# ACme.net
KiCad netlist of a schematic drawn in EAGLE
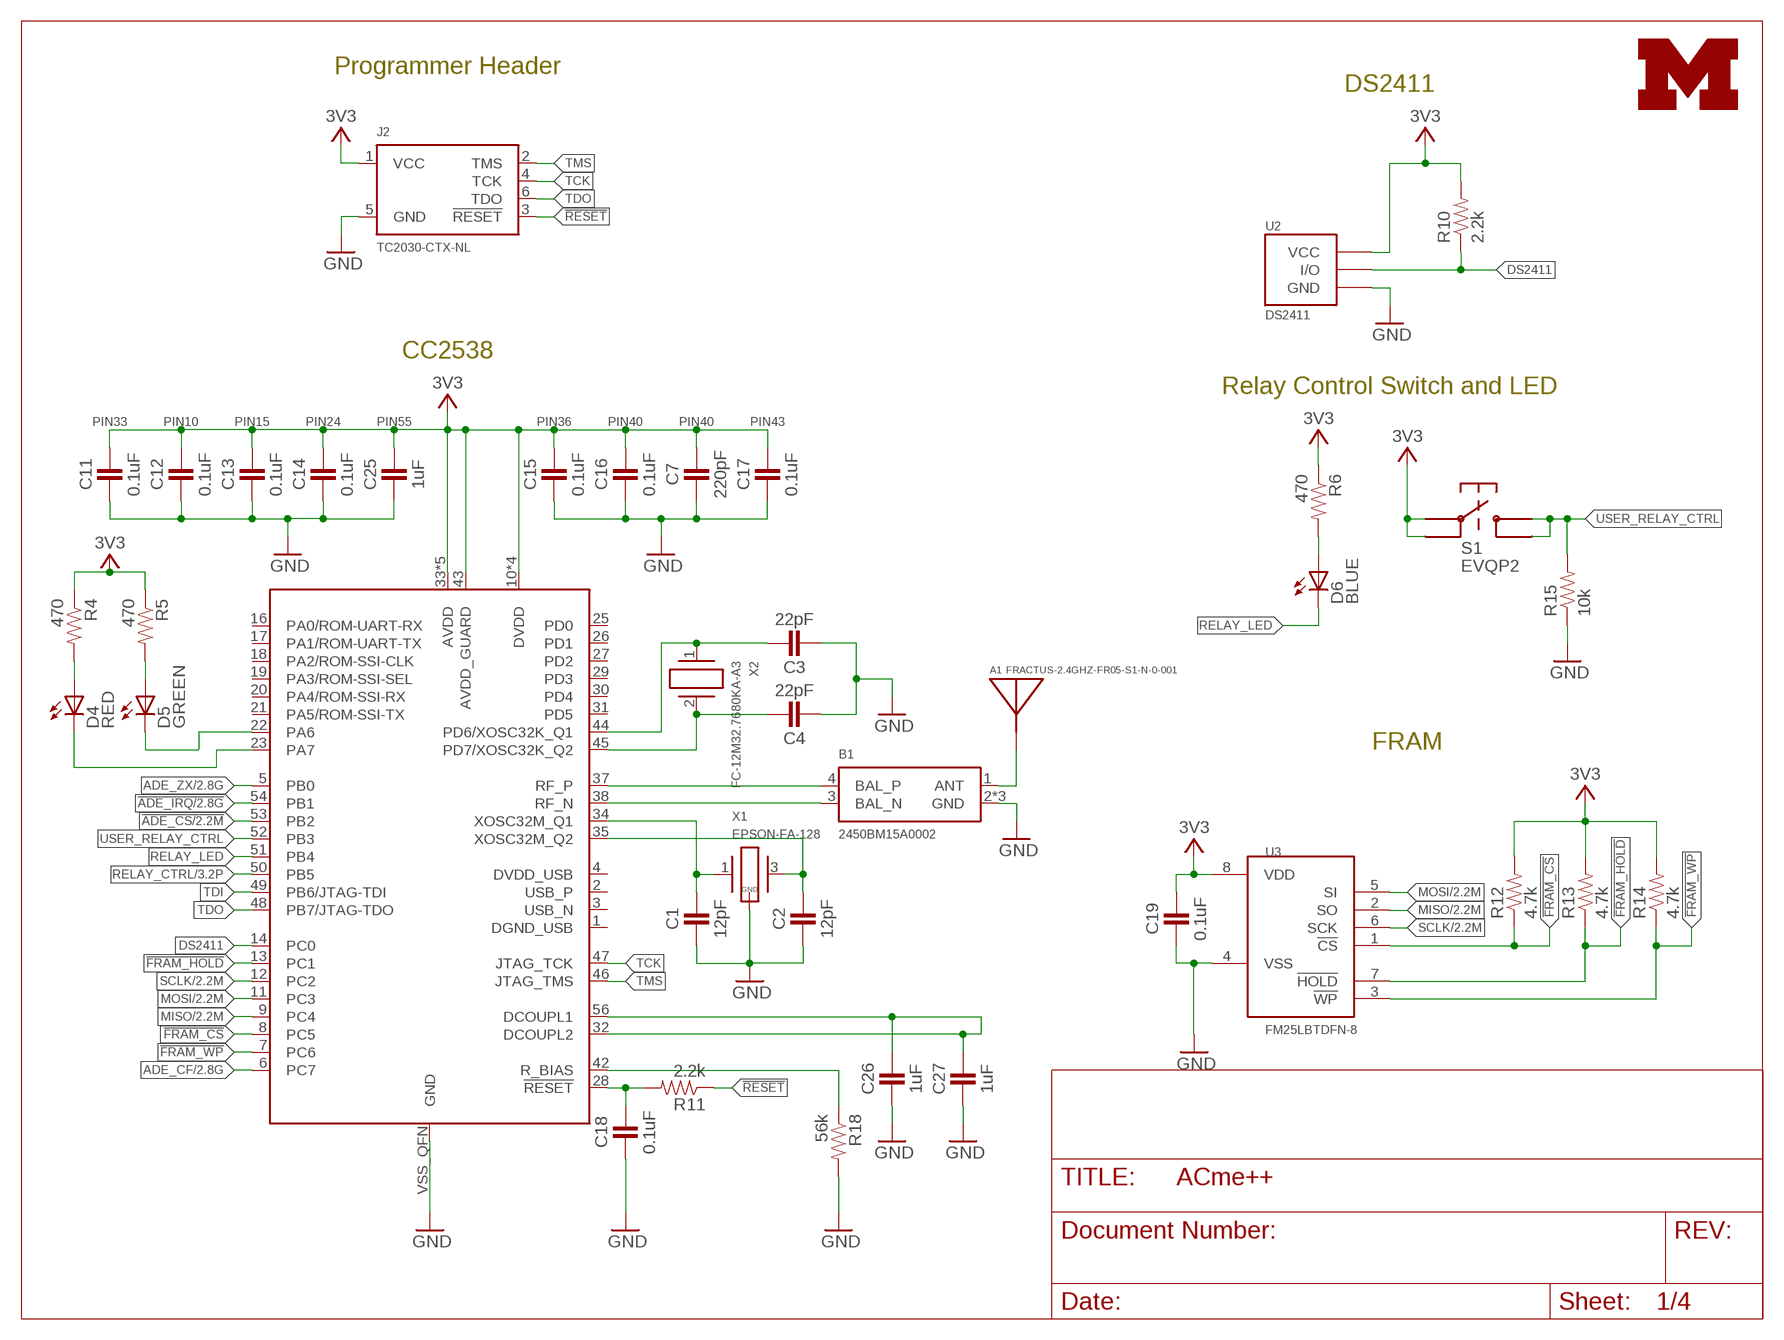
[diagram p0: schematic, sheet 1]
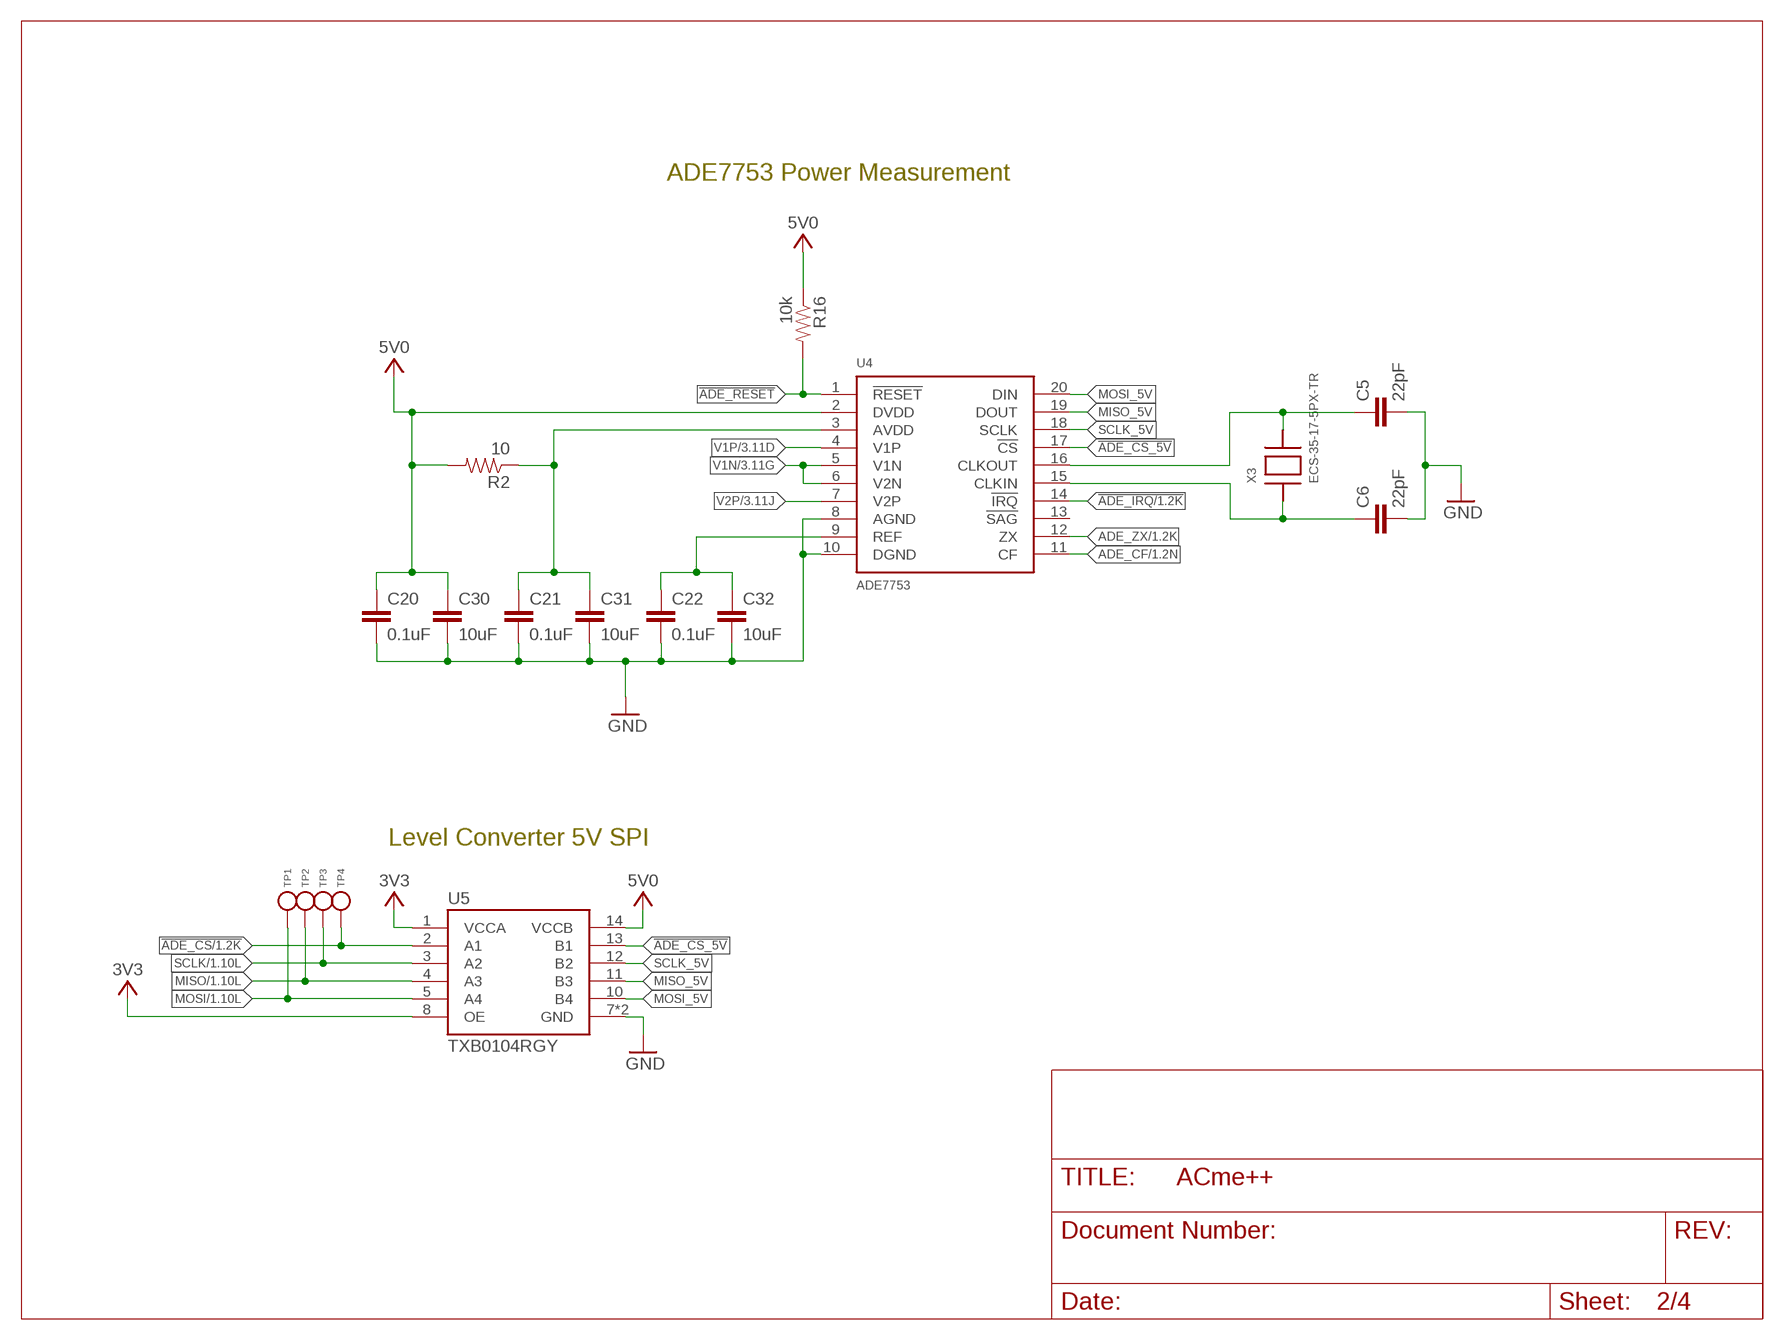
[diagram p1: schematic, sheet 2]
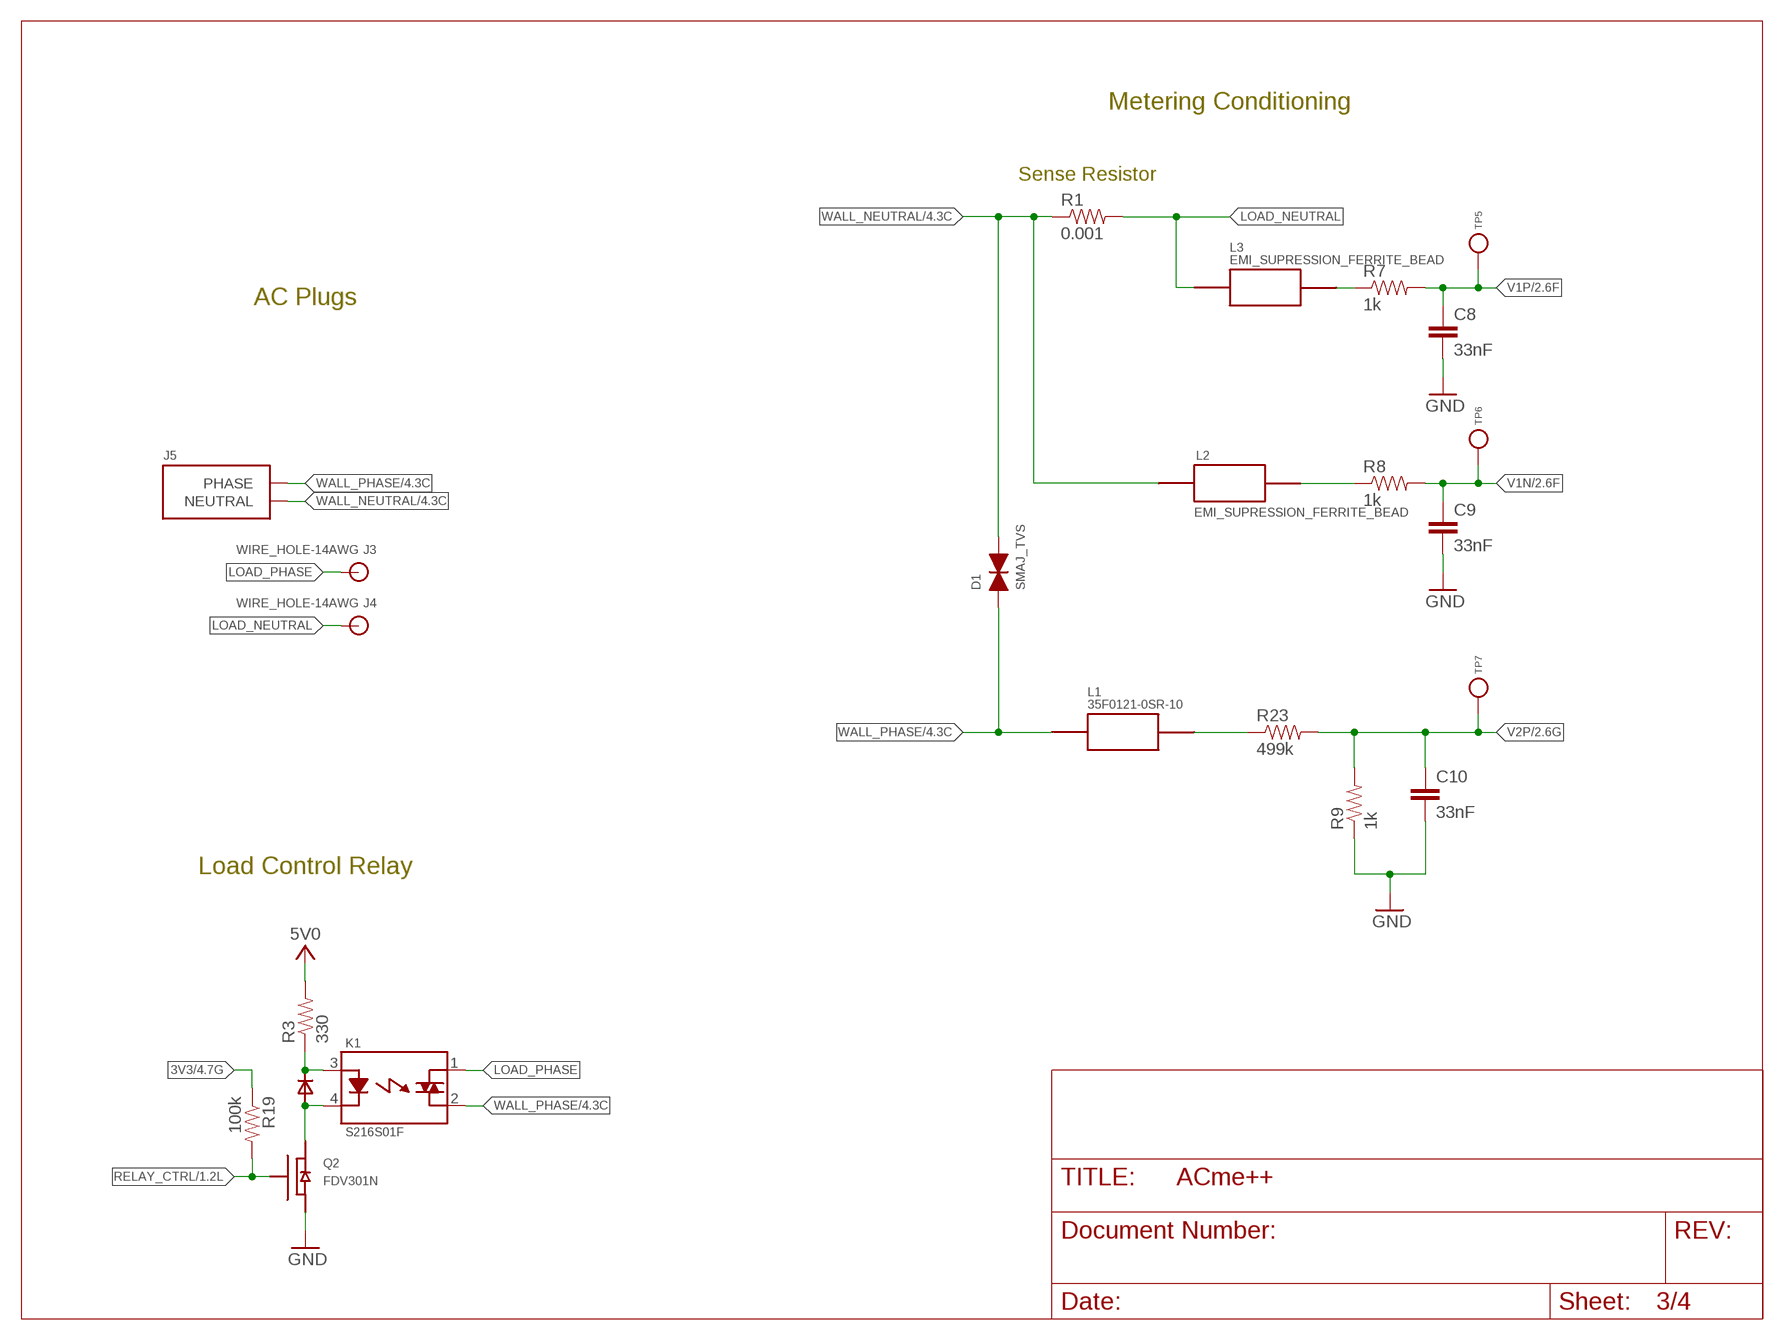
[diagram p2: schematic, sheet 3]
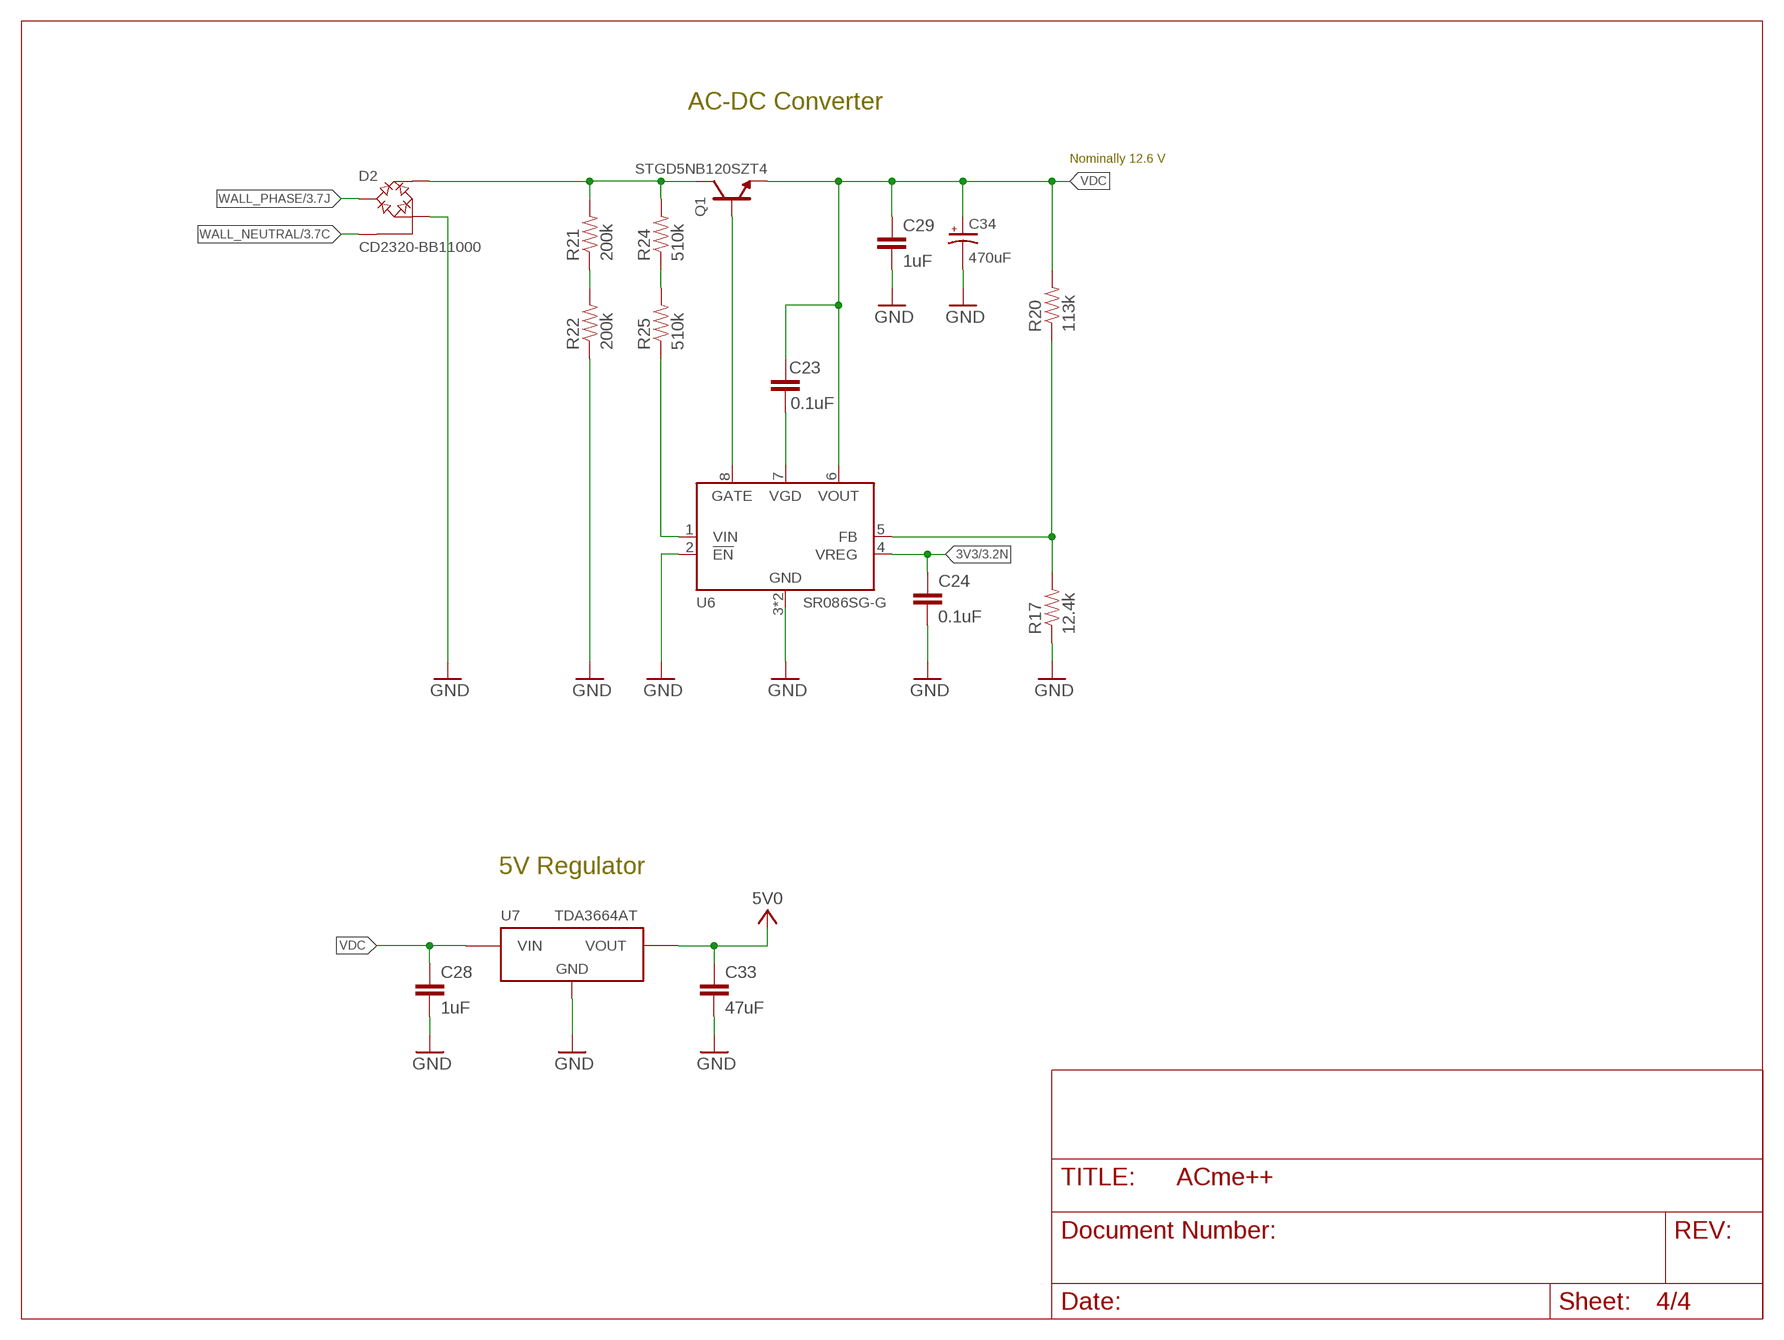
[diagram p3: schematic, sheet 4]

(export (version "E")
  (design (tool "Eeschema 10.0.6"))
  (components
    (comp (ref "C5")
      (value "22pF")
      (footprint "eagle-import:0603-CAP")
      (libsource (lib "eagle-import") (part "CAP0603-CAP"))
    )
    (comp (ref "C6")
      (value "22pF")
      (footprint "eagle-import:0603-CAP")
      (libsource (lib "eagle-import") (part "CAP0603-CAP"))
    )
    (comp (ref "C20")
      (value "0.1uF")
      (footprint "eagle-import:0603-CAP")
      (libsource (lib "eagle-import") (part "CAP0603-CAP"))
    )
    (comp (ref "C21")
      (value "0.1uF")
      (footprint "eagle-import:0603-CAP")
      (libsource (lib "eagle-import") (part "CAP0603-CAP"))
    )
    (comp (ref "C22")
      (value "0.1uF")
      (footprint "eagle-import:0603-CAP")
      (libsource (lib "eagle-import") (part "CAP0603-CAP"))
    )
    (comp (ref "C30")
      (value "10uF")
      (footprint "eagle-import:0603-CAP")
      (libsource (lib "eagle-import") (part "CAP0603-CAP"))
    )
    (comp (ref "C31")
      (value "10uF")
      (footprint "eagle-import:0603-CAP")
      (libsource (lib "eagle-import") (part "CAP0603-CAP"))
    )
    (comp (ref "C32")
      (value "10uF")
      (footprint "eagle-import:0603-CAP")
      (libsource (lib "eagle-import") (part "CAP0603-CAP"))
    )
    (comp (ref "R2")
      (value "10")
      (footprint "eagle-import:0603-RES")
      (libsource (lib "eagle-import") (part "RESISTOR0603-RES"))
    )
    (comp (ref "R16")
      (value "10k")
      (footprint "eagle-import:0603-RES")
      (libsource (lib "eagle-import") (part "RESISTOR0603-RES"))
    )
    (comp (ref "TP1")
      (value "TEST_POINT_0.040IN")
      (footprint "eagle-import:TESTPOINT_0.040IN")
      (libsource (lib "eagle-import") (part "TEST_POINT_0.040IN"))
    )
    (comp (ref "TP2")
      (value "TEST_POINT_0.040IN")
      (footprint "eagle-import:TESTPOINT_0.040IN")
      (libsource (lib "eagle-import") (part "TEST_POINT_0.040IN"))
    )
    (comp (ref "TP3")
      (value "TEST_POINT_0.040IN")
      (footprint "eagle-import:TESTPOINT_0.040IN")
      (libsource (lib "eagle-import") (part "TEST_POINT_0.040IN"))
    )
    (comp (ref "TP4")
      (value "TEST_POINT_0.040IN")
      (footprint "eagle-import:TESTPOINT_0.040IN")
      (libsource (lib "eagle-import") (part "TEST_POINT_0.040IN"))
    )
    (comp (ref "U4")
      (value "ADE7753")
      (footprint "eagle-import:SSOP-20")
      (fields (field (name "MOUSER") " 584-ADE7753ARSZR "))
      (libsource (lib "eagle-import") (part "ADE7753"))
    )
    (comp (ref "U5")
      (value "TXB0104RGY")
      (footprint "eagle-import:S-PVQFN-N14")
      (libsource (lib "eagle-import") (part "TXB0104RGY"))
    )
    (comp (ref "X3")
      (value "ECS-35-17-5PX-TR")
      (footprint "eagle-import:CSM-7X")
      (libsource (lib "eagle-import") (part "ECS-35-17-5PX-TR"))
    )
    (comp (ref "C8")
      (value "33nF")
      (footprint "eagle-import:0805")
      (libsource (lib "eagle-import") (part "CAP0805"))
    )
    (comp (ref "C9")
      (value "33nF")
      (footprint "eagle-import:0805")
      (libsource (lib "eagle-import") (part "CAP0805"))
    )
    (comp (ref "C10")
      (value "33nF")
      (footprint "eagle-import:0805")
      (libsource (lib "eagle-import") (part "CAP0805"))
    )
    (comp (ref "D1")
      (value "SMAJ_TVS")
      (footprint "eagle-import:DO214_TVS")
      (libsource (lib "eagle-import") (part "SMAJ_TVS"))
    )
    (comp (ref "D3")
      (value "DIODE_MMBD914")
      (footprint "eagle-import:SOT-23")
      (libsource (lib "eagle-import") (part "DIODE_MMBD914"))
    )
    (comp (ref "J3")
      (value "WIRE_HOLE-14AWG")
      (footprint "eagle-import:WIRE_HOLE-14AWG")
      (libsource (lib "eagle-import") (part "WIRE_HOLE-14AWG"))
    )
    (comp (ref "J4")
      (value "WIRE_HOLE-14AWG")
      (footprint "eagle-import:WIRE_HOLE-14AWG")
      (libsource (lib "eagle-import") (part "WIRE_HOLE-14AWG"))
    )
    (comp (ref "J5")
      (value "AC-PLUG-2")
      (footprint "eagle-import:AC_MALE_PINS_2")
      (libsource (lib "eagle-import") (part "AC-PLUG-2"))
    )
    (comp (ref "K1")
      (value "S216S01F")
      (footprint "eagle-import:RELAY_SX16S0X")
      (libsource (lib "eagle-import") (part "S216S01F"))
    )
    (comp (ref "L1")
      (value "35F0121-0SR-10")
      (footprint "eagle-import:35F0102")
      (libsource (lib "eagle-import") (part "35F0121-0SR-10"))
    )
    (comp (ref "L2")
      (value "EMI_SUPRESSION_FERRITE_BEAD")
      (footprint "eagle-import:L1806")
      (libsource (lib "eagle-import") (part "EMI_SUPRESSION_FERRITE_BEAD"))
    )
    (comp (ref "L3")
      (value "EMI_SUPRESSION_FERRITE_BEAD")
      (footprint "eagle-import:L1806")
      (libsource (lib "eagle-import") (part "EMI_SUPRESSION_FERRITE_BEAD"))
    )
    (comp (ref "Q2")
      (value "FDV301N")
      (footprint "eagle-import:SOT-23")
      (libsource (lib "eagle-import") (part "FDV301N"))
    )
    (comp (ref "R1")
      (value "0.001")
      (footprint "eagle-import:R2512")
      (libsource (lib "eagle-import") (part "SparkFun-Resistors_RESISTOR2512"))
    )
    (comp (ref "R3")
      (value "330")
      (footprint "eagle-import:0805")
      (libsource (lib "eagle-import") (part "RESISTOR0805-RES"))
    )
    (comp (ref "R7")
      (value "1k")
      (footprint "eagle-import:0805")
      (libsource (lib "eagle-import") (part "RESISTOR0805-RES"))
    )
    (comp (ref "R8")
      (value "1k")
      (footprint "eagle-import:0805")
      (libsource (lib "eagle-import") (part "RESISTOR0805-RES"))
    )
    (comp (ref "R9")
      (value "1k")
      (footprint "eagle-import:0805")
      (libsource (lib "eagle-import") (part "RESISTOR0805-RES"))
    )
    (comp (ref "R19")
      (value "100k")
      (footprint "eagle-import:0603-RES")
      (libsource (lib "eagle-import") (part "RESISTOR0603-RES"))
    )
    (comp (ref "R23")
      (value "499k")
      (footprint "eagle-import:0805")
      (libsource (lib "eagle-import") (part "RESISTOR0805-RES"))
    )
    (comp (ref "TP5")
      (value "TEST_POINT_0.040IN")
      (footprint "eagle-import:TESTPOINT_0.040IN")
      (libsource (lib "eagle-import") (part "TEST_POINT_0.040IN"))
    )
    (comp (ref "TP6")
      (value "TEST_POINT_0.040IN")
      (footprint "eagle-import:TESTPOINT_0.040IN")
      (libsource (lib "eagle-import") (part "TEST_POINT_0.040IN"))
    )
    (comp (ref "TP7")
      (value "TEST_POINT_0.040IN")
      (footprint "eagle-import:TESTPOINT_0.040IN")
      (libsource (lib "eagle-import") (part "TEST_POINT_0.040IN"))
    )
    (comp (ref "C23")
      (value "0.1uF")
      (footprint "eagle-import:0603-CAP")
      (libsource (lib "eagle-import") (part "CAP0603-CAP"))
    )
    (comp (ref "C24")
      (value "0.1uF")
      (footprint "eagle-import:0603-CAP")
      (libsource (lib "eagle-import") (part "CAP0603-CAP"))
    )
    (comp (ref "C28")
      (value "1uF")
      (footprint "eagle-import:0603-CAP")
      (libsource (lib "eagle-import") (part "CAP0603-CAP"))
    )
    (comp (ref "C29")
      (value "1uF")
      (footprint "eagle-import:1206")
      (libsource (lib "eagle-import") (part "CAP1206"))
    )
    (comp (ref "C33")
      (value "47uF")
      (footprint "eagle-import:1206")
      (libsource (lib "eagle-import") (part "CAP1206"))
    )
    (comp (ref "C34")
      (value "470uF")
      (footprint "eagle-import:CAP_SM_10MM")
      (libsource (lib "eagle-import") (part "CAP_EEE-FP1E471AP"))
    )
    (comp (ref "D2")
      (value "CD2320-BB11000")
      (footprint "eagle-import:CD2320")
      (libsource (lib "eagle-import") (part "CD2320-BB11000"))
    )
    (comp (ref "Q1")
      (value "STGD5NB120SZT4")
      (footprint "eagle-import:DPAK")
      (libsource (lib "eagle-import") (part "STGD5NB120SZT4"))
    )
    (comp (ref "R17")
      (value "12.4k")
      (footprint "eagle-import:0603-RES")
      (libsource (lib "eagle-import") (part "SparkFun-Resistors_RESISTOR0603-RES"))
    )
    (comp (ref "R20")
      (value "113k")
      (footprint "eagle-import:0603-RES")
      (libsource (lib "eagle-import") (part "SparkFun-Resistors_RESISTOR0603-RES"))
    )
    (comp (ref "R21")
      (value "200k")
      (footprint "eagle-import:1206")
      (libsource (lib "eagle-import") (part "SparkFun-Resistors_RESISTOR1206"))
    )
    (comp (ref "R22")
      (value "200k")
      (footprint "eagle-import:1206")
      (libsource (lib "eagle-import") (part "SparkFun-Resistors_RESISTOR1206"))
    )
    (comp (ref "R24")
      (value "510k")
      (footprint "eagle-import:1206")
      (libsource (lib "eagle-import") (part "SparkFun-Resistors_RESISTOR1206"))
    )
    (comp (ref "R25")
      (value "510k")
      (footprint "eagle-import:1206")
      (libsource (lib "eagle-import") (part "SparkFun-Resistors_RESISTOR1206"))
    )
    (comp (ref "U6")
      (value "SR086SG-G")
      (footprint "eagle-import:SR086")
      (libsource (lib "eagle-import") (part "SR086SG-G"))
    )
    (comp (ref "U7")
      (value "TDA3664AT")
      (footprint "eagle-import:SOIC_8")
      (libsource (lib "eagle-import") (part "TDA3664AT"))
    )
    (comp (ref "A1")
      (value "FRACTUS-2.4GHZ-FR05-S1-N-0-001")
      (footprint "eagle-import:FRACTUS-ANTENNA-FR05-S1-N-0-001")
      (libsource (lib "eagle-import") (part "FRACTUS-2.4GHZ-FR05-S1-N-0-001"))
    )
    (comp (ref "B1")
      (value "2450BM15A0002")
      (footprint "eagle-import:2450BM")
      (libsource (lib "eagle-import") (part "2450BM15A0002"))
    )
    (comp (ref "C1")
      (value "12pF")
      (footprint "eagle-import:0402_CAP")
      (libsource (lib "eagle-import") (part "CAPACITOR"))
    )
    (comp (ref "C2")
      (value "12pF")
      (footprint "eagle-import:0402_CAP")
      (libsource (lib "eagle-import") (part "CAPACITOR"))
    )
    (comp (ref "C3")
      (value "22pF")
      (footprint "eagle-import:0402_CAP")
      (libsource (lib "eagle-import") (part "CAPACITOR"))
    )
    (comp (ref "C4")
      (value "22pF")
      (footprint "eagle-import:0402_CAP")
      (libsource (lib "eagle-import") (part "CAPACITOR"))
    )
    (comp (ref "C7")
      (value "220pF")
      (footprint "eagle-import:0402_CAP")
      (libsource (lib "eagle-import") (part "CAPACITOR"))
    )
    (comp (ref "C11")
      (value "0.1uF")
      (footprint "eagle-import:0402_CAP")
      (libsource (lib "eagle-import") (part "CAPACITOR"))
    )
    (comp (ref "C12")
      (value "0.1uF")
      (footprint "eagle-import:0402_CAP")
      (libsource (lib "eagle-import") (part "CAPACITOR"))
    )
    (comp (ref "C13")
      (value "0.1uF")
      (footprint "eagle-import:0402_CAP")
      (libsource (lib "eagle-import") (part "CAPACITOR"))
    )
    (comp (ref "C14")
      (value "0.1uF")
      (footprint "eagle-import:0402_CAP")
      (libsource (lib "eagle-import") (part "CAPACITOR"))
    )
    (comp (ref "C15")
      (value "0.1uF")
      (footprint "eagle-import:0402_CAP")
      (libsource (lib "eagle-import") (part "CAPACITOR"))
    )
    (comp (ref "C16")
      (value "0.1uF")
      (footprint "eagle-import:0402_CAP")
      (libsource (lib "eagle-import") (part "CAPACITOR"))
    )
    (comp (ref "C17")
      (value "0.1uF")
      (footprint "eagle-import:0402_CAP")
      (libsource (lib "eagle-import") (part "CAPACITOR"))
    )
    (comp (ref "C18")
      (value "0.1uF")
      (footprint "eagle-import:0402_CAP")
      (libsource (lib "eagle-import") (part "CAPACITOR"))
    )
    (comp (ref "C19")
      (value "0.1uF")
      (footprint "eagle-import:0402_CAP")
      (libsource (lib "eagle-import") (part "CAPACITOR"))
    )
    (comp (ref "C25")
      (value "1uF")
      (footprint "eagle-import:0402_CAP")
      (libsource (lib "eagle-import") (part "CAPACITOR"))
    )
    (comp (ref "C26")
      (value "1uF")
      (footprint "eagle-import:0402_CAP")
      (libsource (lib "eagle-import") (part "CAPACITOR"))
    )
    (comp (ref "C27")
      (value "1uF")
      (footprint "eagle-import:0402_CAP")
      (libsource (lib "eagle-import") (part "CAPACITOR"))
    )
    (comp (ref "D4")
      (value "RED")
      (footprint "eagle-import:LED-0603")
      (libsource (lib "eagle-import") (part "LED0603"))
    )
    (comp (ref "D5")
      (value "GREEN")
      (footprint "eagle-import:LED-0603")
      (libsource (lib "eagle-import") (part "LED0603"))
    )
    (comp (ref "D6")
      (value "BLUE")
      (footprint "eagle-import:LED-0603")
      (libsource (lib "eagle-import") (part "LED0603"))
    )
    (comp (ref "J2")
      (value "TC2030-CTX-NL")
      (footprint "eagle-import:TC2030-IDC-NL")
      (libsource (lib "eagle-import") (part "TC2030-CTX-NL"))
    )
    (comp (ref "R4")
      (value "470")
      (footprint "eagle-import:0402_RES")
      (libsource (lib "eagle-import") (part "passives_RESISTOR"))
    )
    (comp (ref "R5")
      (value "470")
      (footprint "eagle-import:0402_RES")
      (libsource (lib "eagle-import") (part "passives_RESISTOR"))
    )
    (comp (ref "R6")
      (value "470")
      (footprint "eagle-import:0402_RES")
      (libsource (lib "eagle-import") (part "passives_RESISTOR"))
    )
    (comp (ref "R10")
      (value "2.2k")
      (footprint "eagle-import:0402_RES")
      (libsource (lib "eagle-import") (part "passives_RESISTOR"))
    )
    (comp (ref "R11")
      (value "2.2k")
      (footprint "eagle-import:0402_RES")
      (libsource (lib "eagle-import") (part "passives_RESISTOR"))
    )
    (comp (ref "R12")
      (value "4.7k")
      (footprint "eagle-import:0402_RES")
      (libsource (lib "eagle-import") (part "passives_RESISTOR"))
    )
    (comp (ref "R13")
      (value "4.7k")
      (footprint "eagle-import:0402_RES")
      (libsource (lib "eagle-import") (part "passives_RESISTOR"))
    )
    (comp (ref "R14")
      (value "4.7k")
      (footprint "eagle-import:0402_RES")
      (libsource (lib "eagle-import") (part "passives_RESISTOR"))
    )
    (comp (ref "R15")
      (value "10k")
      (footprint "eagle-import:0603-RES")
      (libsource (lib "eagle-import") (part "RESISTOR0603-RES"))
    )
    (comp (ref "R18")
      (value "56k")
      (footprint "eagle-import:0402_RES")
      (libsource (lib "eagle-import") (part "passives_RESISTOR"))
    )
    (comp (ref "S1")
      (value "EVQP2")
      (footprint "eagle-import:EVQP2")
      (libsource (lib "eagle-import") (part "EVQP2"))
    )
    (comp (ref "U$3")
      (value "UMICH_SOLID_MEDIUM")
      (footprint "eagle-import:UMICH_SOLID_200MIL")
      (libsource (lib "eagle-import") (part "UMICH_SOLID_MEDIUM"))
    )
    (comp (ref "U1")
      (value "CC2538")
      (footprint "eagle-import:S-PVQFN-N56")
      (libsource (lib "eagle-import") (part "CC2538"))
    )
    (comp (ref "U2")
      (value "DS2411")
      (footprint "eagle-import:SOT-23")
      (libsource (lib "eagle-import") (part "DS2411"))
    )
    (comp (ref "U3")
      (value "FM25LBTDFN-8")
      (footprint "eagle-import:TDFN-8")
      (libsource (lib "eagle-import") (part "FM25LBTDFN-8"))
    )
    (comp (ref "X1")
      (value "EPSON-FA-128")
      (footprint "eagle-import:FA-128")
      (libsource (lib "eagle-import") (part "EPSON-FA-128"))
    )
    (comp (ref "X2")
      (value "FC-12M32.7680KA-A3")
      (footprint "eagle-import:FC-12M")
      (libsource (lib "eagle-import") (part "FC-12M32.7680KA-A3"))
    )
  )
  (nets
    (net (code "1") (name "3V3") (class "Default")
      (node (ref "C11") (pin "1") (pinfunction "1_1") (pintype "bidirectional"))
      (node (ref "C12") (pin "1") (pinfunction "1_1") (pintype "bidirectional"))
      (node (ref "C13") (pin "1") (pinfunction "1_1") (pintype "bidirectional"))
      (node (ref "C14") (pin "1") (pinfunction "1_1") (pintype "bidirectional"))
      (node (ref "C15") (pin "1") (pinfunction "1_1") (pintype "bidirectional"))
      (node (ref "C16") (pin "1") (pinfunction "1_1") (pintype "bidirectional"))
      (node (ref "C17") (pin "1") (pinfunction "1_1") (pintype "bidirectional"))
      (node (ref "C19") (pin "1") (pinfunction "1_1") (pintype "bidirectional"))
      (node (ref "C24") (pin "1") (pinfunction "1_1") (pintype "passive"))
      (node (ref "C25") (pin "1") (pinfunction "1_1") (pintype "bidirectional"))
      (node (ref "C7") (pin "1") (pinfunction "1_1") (pintype "bidirectional"))
      (node (ref "J2") (pin "1") (pinfunction "VCC_1") (pintype "bidirectional"))
      (node (ref "R10") (pin "2") (pinfunction "2_2") (pintype "passive"))
      (node (ref "R12") (pin "2") (pinfunction "2_2") (pintype "passive"))
      (node (ref "R13") (pin "2") (pinfunction "2_2") (pintype "passive"))
      (node (ref "R14") (pin "2") (pinfunction "2_2") (pintype "passive"))
      (node (ref "R19") (pin "1") (pinfunction "1_1") (pintype "passive"))
      (node (ref "R4") (pin "1") (pinfunction "1_1") (pintype "passive"))
      (node (ref "R5") (pin "1") (pinfunction "1_1") (pintype "passive"))
      (node (ref "R6") (pin "1") (pinfunction "1_1") (pintype "passive"))
      (node (ref "S1") (pin "P$1") (pinfunction "P$1_P$1") (pintype "passive"))
      (node (ref "S1") (pin "P$3") (pinfunction "P$3_P$3") (pintype "passive"))
      (node (ref "U1") (pin "10") (pinfunction "DVDD_10") (pintype "bidirectional"))
      (node (ref "U1") (pin "15") (pinfunction "DVDD_15") (pintype "bidirectional"))
      (node (ref "U1") (pin "24") (pinfunction "DVDD_24") (pintype "bidirectional"))
      (node (ref "U1") (pin "33") (pinfunction "AVDD_33") (pintype "bidirectional"))
      (node (ref "U1") (pin "36") (pinfunction "AVDD_36") (pintype "bidirectional"))
      (node (ref "U1") (pin "39") (pinfunction "AVDD_39") (pintype "bidirectional"))
      (node (ref "U1") (pin "40") (pinfunction "AVDD_40") (pintype "bidirectional"))
      (node (ref "U1") (pin "41") (pinfunction "AVDD_41") (pintype "bidirectional"))
      (node (ref "U1") (pin "43") (pinfunction "AVDD_GUARD_43") (pintype "bidirectional"))
      (node (ref "U1") (pin "55") (pinfunction "DVDD_55") (pintype "bidirectional"))
      (node (ref "U2") (pin "2") (pinfunction "VCC_2") (pintype "bidirectional"))
      (node (ref "U3") (pin "8") (pinfunction "VDD_8") (pintype "bidirectional"))
      (node (ref "U5") (pin "1") (pinfunction "VCCA_1") (pintype "bidirectional"))
      (node (ref "U5") (pin "8") (pinfunction "OE_8") (pintype "bidirectional"))
      (node (ref "U6") (pin "4") (pinfunction "VREG_4") (pintype "bidirectional"))
    )
    (net (code "2") (name "5V0") (class "Default")
      (node (ref "C20") (pin "1") (pinfunction "1_1") (pintype "passive"))
      (node (ref "C30") (pin "1") (pinfunction "1_1") (pintype "passive"))
      (node (ref "C33") (pin "1") (pinfunction "1_1") (pintype "passive"))
      (node (ref "R16") (pin "1") (pinfunction "1_1") (pintype "passive"))
      (node (ref "R2") (pin "2") (pinfunction "2_2") (pintype "passive"))
      (node (ref "R3") (pin "2") (pinfunction "2_2") (pintype "passive"))
      (node (ref "U4") (pin "2") (pinfunction "DVDD_2") (pintype "bidirectional"))
      (node (ref "U5") (pin "14") (pinfunction "VCCB_14") (pintype "bidirectional"))
      (node (ref "U7") (pin "1") (pinfunction "VOUT_1") (pintype "bidirectional"))
    )
    (net (code "3") (name "ADE_CF") (class "Default")
      (node (ref "U1") (pin "6") (pinfunction "PC7_6") (pintype "bidirectional"))
      (node (ref "U4") (pin "11") (pinfunction "CF_11") (pintype "bidirectional"))
    )
    (net (code "4") (name "ADE_ZX") (class "Default")
      (node (ref "U1") (pin "5") (pinfunction "PB0_5") (pintype "bidirectional"))
      (node (ref "U4") (pin "12") (pinfunction "ZX_12") (pintype "bidirectional"))
    )
    (net (code "5") (name "DS2411") (class "Default")
      (node (ref "R10") (pin "1") (pinfunction "1_1") (pintype "passive"))
      (node (ref "U1") (pin "14") (pinfunction "PC0_14") (pintype "bidirectional"))
      (node (ref "U2") (pin "1") (pinfunction "I/O_1") (pintype "bidirectional"))
    )
    (net (code "6") (name "GND") (class "Default")
      (node (ref "B1") (pin "2") (pinfunction "GND_2") (pintype "bidirectional"))
      (node (ref "B1") (pin "5") (pinfunction "GND_5") (pintype "bidirectional"))
      (node (ref "B1") (pin "6") (pinfunction "GND_6") (pintype "bidirectional"))
      (node (ref "C1") (pin "2") (pinfunction "2_2") (pintype "bidirectional"))
      (node (ref "C10") (pin "2") (pinfunction "2_2") (pintype "passive"))
      (node (ref "C11") (pin "2") (pinfunction "2_2") (pintype "bidirectional"))
      (node (ref "C12") (pin "2") (pinfunction "2_2") (pintype "bidirectional"))
      (node (ref "C13") (pin "2") (pinfunction "2_2") (pintype "bidirectional"))
      (node (ref "C14") (pin "2") (pinfunction "2_2") (pintype "bidirectional"))
      (node (ref "C15") (pin "2") (pinfunction "2_2") (pintype "bidirectional"))
      (node (ref "C16") (pin "2") (pinfunction "2_2") (pintype "bidirectional"))
      (node (ref "C17") (pin "2") (pinfunction "2_2") (pintype "bidirectional"))
      (node (ref "C18") (pin "2") (pinfunction "2_2") (pintype "bidirectional"))
      (node (ref "C19") (pin "2") (pinfunction "2_2") (pintype "bidirectional"))
      (node (ref "C2") (pin "2") (pinfunction "2_2") (pintype "bidirectional"))
      (node (ref "C20") (pin "2") (pinfunction "2_2") (pintype "passive"))
      (node (ref "C21") (pin "2") (pinfunction "2_2") (pintype "passive"))
      (node (ref "C22") (pin "2") (pinfunction "2_2") (pintype "passive"))
      (node (ref "C24") (pin "2") (pinfunction "2_2") (pintype "passive"))
      (node (ref "C25") (pin "2") (pinfunction "2_2") (pintype "bidirectional"))
      (node (ref "C26") (pin "2") (pinfunction "2_2") (pintype "bidirectional"))
      (node (ref "C27") (pin "2") (pinfunction "2_2") (pintype "bidirectional"))
      (node (ref "C28") (pin "2") (pinfunction "2_2") (pintype "passive"))
      (node (ref "C29") (pin "2") (pinfunction "2_2") (pintype "passive"))
      (node (ref "C3") (pin "2") (pinfunction "2_2") (pintype "bidirectional"))
      (node (ref "C30") (pin "2") (pinfunction "2_2") (pintype "passive"))
      (node (ref "C31") (pin "2") (pinfunction "2_2") (pintype "passive"))
      (node (ref "C32") (pin "2") (pinfunction "2_2") (pintype "passive"))
      (node (ref "C33") (pin "2") (pinfunction "2_2") (pintype "passive"))
      (node (ref "C34") (pin "-") (pinfunction "-_-") (pintype "bidirectional"))
      (node (ref "C4") (pin "2") (pinfunction "2_2") (pintype "bidirectional"))
      (node (ref "C5") (pin "2") (pinfunction "2_2") (pintype "passive"))
      (node (ref "C6") (pin "2") (pinfunction "2_2") (pintype "passive"))
      (node (ref "C7") (pin "2") (pinfunction "2_2") (pintype "bidirectional"))
      (node (ref "C8") (pin "2") (pinfunction "2_2") (pintype "passive"))
      (node (ref "C9") (pin "2") (pinfunction "2_2") (pintype "passive"))
      (node (ref "D2") (pin "4") (pinfunction "NEG_4") (pintype "bidirectional"))
      (node (ref "J2") (pin "5") (pinfunction "GND_5") (pintype "bidirectional"))
      (node (ref "Q2") (pin "2") (pinfunction "S_2") (pintype "bidirectional"))
      (node (ref "R15") (pin "1") (pinfunction "1_1") (pintype "passive"))
      (node (ref "R17") (pin "1") (pinfunction "1_1") (pintype "passive"))
      (node (ref "R18") (pin "2") (pinfunction "2_2") (pintype "passive"))
      (node (ref "R22") (pin "1") (pinfunction "1_1") (pintype "passive"))
      (node (ref "R9") (pin "1") (pinfunction "1_1") (pintype "passive"))
      (node (ref "U1") (pin "VSS_QFN") (pinfunction "GND_VSS_QFN") (pintype "bidirectional"))
      (node (ref "U2") (pin "3") (pinfunction "GND_3") (pintype "bidirectional"))
      (node (ref "U3") (pin "4") (pinfunction "VSS_4") (pintype "bidirectional"))
      (node (ref "U4") (pin "10") (pinfunction "DGND_10") (pintype "bidirectional"))
      (node (ref "U4") (pin "8") (pinfunction "AGND_8") (pintype "bidirectional"))
      (node (ref "U5") (pin "7") (pinfunction "GND_7") (pintype "bidirectional"))
      (node (ref "U5") (pin "THERMALPAD") (pinfunction "GND_THERMALPAD") (pintype "bidirectional"))
      (node (ref "U6") (pin "2") (pinfunction "~{EN}_2") (pintype "bidirectional"))
      (node (ref "U6") (pin "3") (pinfunction "GND_3") (pintype "bidirectional"))
      (node (ref "U6") (pin "PAD") (pinfunction "GND_PAD") (pintype "bidirectional"))
      (node (ref "U7") (pin "3") (pinfunction "GND_3") (pintype "bidirectional"))
      (node (ref "X1") (pin "2") (pinfunction "GND_2") (pintype "bidirectional"))
      (node (ref "X1") (pin "4") (pinfunction "GND_4") (pintype "bidirectional"))
    )
    (net (code "7") (name "LOAD_NEUTRAL") (class "Default")
      (node (ref "J4") (pin "P$1") (pinfunction "P$1_P$1") (pintype "bidirectional"))
      (node (ref "L3") (pin "P$1") (pinfunction "P$1_P$1") (pintype "bidirectional"))
      (node (ref "R1") (pin "2") (pinfunction "2_2") (pintype "passive"))
    )
    (net (code "8") (name "LOAD_PHASE") (class "Default")
      (node (ref "J3") (pin "P$1") (pinfunction "P$1_P$1") (pintype "bidirectional"))
      (node (ref "K1") (pin "1") (pinfunction "1_1") (pintype "bidirectional"))
    )
    (net (code "9") (name "MISO") (class "Default")
      (node (ref "TP2") (pin "TESTPOINT") (pinfunction "TESTPOINT_TESTPOINT") (pintype "bidirectional"))
      (node (ref "U1") (pin "9") (pinfunction "PC4_9") (pintype "bidirectional"))
      (node (ref "U3") (pin "2") (pinfunction "SO_2") (pintype "bidirectional"))
      (node (ref "U5") (pin "4") (pinfunction "A3_4") (pintype "bidirectional"))
    )
    (net (code "10") (name "MISO_5V") (class "Default")
      (node (ref "U4") (pin "19") (pinfunction "DOUT_19") (pintype "bidirectional"))
      (node (ref "U5") (pin "11") (pinfunction "B3_11") (pintype "bidirectional"))
    )
    (net (code "11") (name "MOSI") (class "Default")
      (node (ref "TP1") (pin "TESTPOINT") (pinfunction "TESTPOINT_TESTPOINT") (pintype "bidirectional"))
      (node (ref "U1") (pin "11") (pinfunction "PC3_11") (pintype "bidirectional"))
      (node (ref "U3") (pin "5") (pinfunction "SI_5") (pintype "bidirectional"))
      (node (ref "U5") (pin "5") (pinfunction "A4_5") (pintype "bidirectional"))
    )
    (net (code "12") (name "MOSI_5V") (class "Default")
      (node (ref "U4") (pin "20") (pinfunction "DIN_20") (pintype "bidirectional"))
      (node (ref "U5") (pin "10") (pinfunction "B4_10") (pintype "bidirectional"))
    )
    (net (code "13") (name "Net-(A1-ANTENNA)") (class "Default")
      (node (ref "A1") (pin "1") (pinfunction "ANTENNA_1") (pintype "bidirectional"))
      (node (ref "B1") (pin "1") (pinfunction "ANT_1") (pintype "bidirectional"))
    )
    (net (code "14") (name "Net-(B1-BAL_N)") (class "Default")
      (node (ref "B1") (pin "3") (pinfunction "BAL_N_3") (pintype "bidirectional"))
      (node (ref "U1") (pin "38") (pinfunction "RF_N_38") (pintype "bidirectional"))
    )
    (net (code "15") (name "Net-(B1-BAL_P)") (class "Default")
      (node (ref "B1") (pin "4") (pinfunction "BAL_P_4") (pintype "bidirectional"))
      (node (ref "U1") (pin "37") (pinfunction "RF_P_37") (pintype "bidirectional"))
    )
    (net (code "16") (name "Net-(D2-POS)") (class "Default")
      (node (ref "D2") (pin "3") (pinfunction "POS_3") (pintype "bidirectional"))
      (node (ref "Q1") (pin "P$2") (pinfunction "C_P$2") (pintype "bidirectional"))
      (node (ref "R21") (pin "2") (pinfunction "2_2") (pintype "passive"))
      (node (ref "R24") (pin "2") (pinfunction "2_2") (pintype "passive"))
    )
    (net (code "17") (name "Net-(D3-1)") (class "Default")
      (node (ref "D3") (pin "3") (pinfunction "1_3") (pintype "bidirectional"))
      (node (ref "K1") (pin "3") (pinfunction "3_3") (pintype "bidirectional"))
      (node (ref "R3") (pin "1") (pinfunction "1_1") (pintype "passive"))
    )
    (net (code "18") (name "Net-(D3-2)") (class "Default")
      (node (ref "D3") (pin "1") (pinfunction "2_1") (pintype "bidirectional"))
      (node (ref "K1") (pin "4") (pinfunction "4_4") (pintype "bidirectional"))
      (node (ref "Q2") (pin "3") (pinfunction "D_3") (pintype "bidirectional"))
    )
    (net (code "19") (name "Net-(D4-PadA)") (class "Default")
      (node (ref "D4") (pin "A") (pinfunction "A_A") (pintype "passive"))
      (node (ref "R4") (pin "2") (pinfunction "2_2") (pintype "passive"))
    )
    (net (code "20") (name "Net-(D5-PadA)") (class "Default")
      (node (ref "D5") (pin "A") (pinfunction "A_A") (pintype "passive"))
      (node (ref "R5") (pin "2") (pinfunction "2_2") (pintype "passive"))
    )
    (net (code "21") (name "Net-(D6-PadA)") (class "Default")
      (node (ref "D6") (pin "A") (pinfunction "A_A") (pintype "passive"))
      (node (ref "R6") (pin "2") (pinfunction "2_2") (pintype "passive"))
    )
    (net (code "22") (name "Net-(L1-P$2)") (class "Default")
      (node (ref "L1") (pin "2") (pinfunction "P$2_2") (pintype "bidirectional"))
      (node (ref "R23") (pin "1") (pinfunction "1_1") (pintype "passive"))
    )
    (net (code "23") (name "Net-(L2-PadP$2)") (class "Default")
      (node (ref "L2") (pin "P$2") (pinfunction "P$2_P$2") (pintype "bidirectional"))
      (node (ref "R8") (pin "1") (pinfunction "1_1") (pintype "passive"))
    )
    (net (code "24") (name "Net-(L3-PadP$2)") (class "Default")
      (node (ref "L3") (pin "P$2") (pinfunction "P$2_P$2") (pintype "bidirectional"))
      (node (ref "R7") (pin "1") (pinfunction "1_1") (pintype "passive"))
    )
    (net (code "25") (name "Net-(Q1-G)") (class "Default")
      (node (ref "Q1") (pin "P$1") (pinfunction "G_P$1") (pintype "bidirectional"))
      (node (ref "U6") (pin "8") (pinfunction "GATE_8") (pintype "bidirectional"))
    )
    (net (code "26") (name "Net-(R21-Pad1)") (class "Default")
      (node (ref "R21") (pin "1") (pinfunction "1_1") (pintype "passive"))
      (node (ref "R22") (pin "2") (pinfunction "2_2") (pintype "passive"))
    )
    (net (code "27") (name "Net-(R24-Pad1)") (class "Default")
      (node (ref "R24") (pin "1") (pinfunction "1_1") (pintype "passive"))
      (node (ref "R25") (pin "2") (pinfunction "2_2") (pintype "passive"))
    )
    (net (code "28") (name "Net-(U1-DCOUPL1)") (class "Default")
      (node (ref "C26") (pin "1") (pinfunction "1_1") (pintype "bidirectional"))
      (node (ref "C27") (pin "1") (pinfunction "1_1") (pintype "bidirectional"))
      (node (ref "U1") (pin "32") (pinfunction "DCOUPL2_32") (pintype "bidirectional"))
      (node (ref "U1") (pin "56") (pinfunction "DCOUPL1_56") (pintype "bidirectional"))
    )
    (net (code "29") (name "Net-(U1-PA6)") (class "Default")
      (node (ref "D5") (pin "C") (pinfunction "C_C") (pintype "passive"))
      (node (ref "U1") (pin "22") (pinfunction "PA6_22") (pintype "bidirectional"))
    )
    (net (code "30") (name "Net-(U1-PA7)") (class "Default")
      (node (ref "D4") (pin "C") (pinfunction "C_C") (pintype "passive"))
      (node (ref "U1") (pin "23") (pinfunction "PA7_23") (pintype "bidirectional"))
    )
    (net (code "31") (name "Net-(U1-PD6{slash}XOSC32K_Q1)") (class "Default")
      (node (ref "C3") (pin "1") (pinfunction "1_1") (pintype "bidirectional"))
      (node (ref "U1") (pin "44") (pinfunction "PD6/XOSC32K_Q1_44") (pintype "bidirectional"))
      (node (ref "X2") (pin "1") (pinfunction "1_1") (pintype "bidirectional"))
    )
    (net (code "32") (name "Net-(U1-PD7{slash}XOSC32K_Q2)") (class "Default")
      (node (ref "C4") (pin "1") (pinfunction "1_1") (pintype "bidirectional"))
      (node (ref "U1") (pin "45") (pinfunction "PD7/XOSC32K_Q2_45") (pintype "bidirectional"))
      (node (ref "X2") (pin "2") (pinfunction "2_2") (pintype "bidirectional"))
    )
    (net (code "33") (name "Net-(U1-R_BIAS)") (class "Default")
      (node (ref "R18") (pin "1") (pinfunction "1_1") (pintype "passive"))
      (node (ref "U1") (pin "42") (pinfunction "R_BIAS_42") (pintype "bidirectional"))
    )
    (net (code "34") (name "Net-(U1-XOSC32M_Q1)") (class "Default")
      (node (ref "C1") (pin "1") (pinfunction "1_1") (pintype "bidirectional"))
      (node (ref "U1") (pin "34") (pinfunction "XOSC32M_Q1_34") (pintype "bidirectional"))
      (node (ref "X1") (pin "1") (pinfunction "1_1") (pintype "bidirectional"))
    )
    (net (code "35") (name "Net-(U1-XOSC32M_Q2)") (class "Default")
      (node (ref "C2") (pin "1") (pinfunction "1_1") (pintype "bidirectional"))
      (node (ref "U1") (pin "35") (pinfunction "XOSC32M_Q2_35") (pintype "bidirectional"))
      (node (ref "X1") (pin "3") (pinfunction "2_3") (pintype "bidirectional"))
    )
    (net (code "36") (name "Net-(U1-~{RESET})") (class "Default")
      (node (ref "C18") (pin "1") (pinfunction "1_1") (pintype "bidirectional"))
      (node (ref "R11") (pin "2") (pinfunction "2_2") (pintype "passive"))
      (node (ref "U1") (pin "28") (pinfunction "~{RESET}_28") (pintype "bidirectional"))
    )
    (net (code "37") (name "Net-(U4-AVDD)") (class "Default")
      (node (ref "C21") (pin "1") (pinfunction "1_1") (pintype "passive"))
      (node (ref "C31") (pin "1") (pinfunction "1_1") (pintype "passive"))
      (node (ref "R2") (pin "1") (pinfunction "1_1") (pintype "passive"))
      (node (ref "U4") (pin "3") (pinfunction "AVDD_3") (pintype "bidirectional"))
    )
    (net (code "38") (name "Net-(U4-CLKIN)") (class "Default")
      (node (ref "C6") (pin "1") (pinfunction "1_1") (pintype "passive"))
      (node (ref "U4") (pin "15") (pinfunction "CLKIN_15") (pintype "bidirectional"))
      (node (ref "X3") (pin "1") (pinfunction "P$1_1") (pintype "bidirectional"))
    )
    (net (code "39") (name "Net-(U4-CLKOUT)") (class "Default")
      (node (ref "C5") (pin "1") (pinfunction "1_1") (pintype "passive"))
      (node (ref "U4") (pin "16") (pinfunction "CLKOUT_16") (pintype "bidirectional"))
      (node (ref "X3") (pin "2") (pinfunction "P$2_2") (pintype "bidirectional"))
    )
    (net (code "40") (name "Net-(U4-REF)") (class "Default")
      (node (ref "C22") (pin "1") (pinfunction "1_1") (pintype "passive"))
      (node (ref "C32") (pin "1") (pinfunction "1_1") (pintype "passive"))
      (node (ref "U4") (pin "9") (pinfunction "REF_9") (pintype "bidirectional"))
    )
    (net (code "41") (name "Net-(U6-FB)") (class "Default")
      (node (ref "R17") (pin "2") (pinfunction "2_2") (pintype "passive"))
      (node (ref "R20") (pin "1") (pinfunction "1_1") (pintype "passive"))
      (node (ref "U6") (pin "5") (pinfunction "FB_5") (pintype "bidirectional"))
    )
    (net (code "42") (name "Net-(U6-VGD)") (class "Default")
      (node (ref "C23") (pin "2") (pinfunction "2_2") (pintype "passive"))
      (node (ref "U6") (pin "7") (pinfunction "VGD_7") (pintype "bidirectional"))
    )
    (net (code "43") (name "Net-(U6-VIN)") (class "Default")
      (node (ref "R25") (pin "1") (pinfunction "1_1") (pintype "passive"))
      (node (ref "U6") (pin "1") (pinfunction "VIN_1") (pintype "bidirectional"))
    )
    (net (code "44") (name "RELAY_CTRL") (class "Default")
      (node (ref "Q2") (pin "1") (pinfunction "G_1") (pintype "bidirectional"))
      (node (ref "R19") (pin "2") (pinfunction "2_2") (pintype "passive"))
      (node (ref "U1") (pin "50") (pinfunction "PB5_50") (pintype "bidirectional"))
    )
    (net (code "45") (name "RELAY_LED") (class "Default")
      (node (ref "D6") (pin "C") (pinfunction "C_C") (pintype "passive"))
      (node (ref "U1") (pin "51") (pinfunction "PB4_51") (pintype "bidirectional"))
    )
    (net (code "46") (name "SCLK") (class "Default")
      (node (ref "TP3") (pin "TESTPOINT") (pinfunction "TESTPOINT_TESTPOINT") (pintype "bidirectional"))
      (node (ref "U1") (pin "12") (pinfunction "PC2_12") (pintype "bidirectional"))
      (node (ref "U3") (pin "6") (pinfunction "SCK_6") (pintype "bidirectional"))
      (node (ref "U5") (pin "3") (pinfunction "A2_3") (pintype "bidirectional"))
    )
    (net (code "47") (name "SCLK_5V") (class "Default")
      (node (ref "U4") (pin "18") (pinfunction "SCLK_18") (pintype "bidirectional"))
      (node (ref "U5") (pin "12") (pinfunction "B2_12") (pintype "bidirectional"))
    )
    (net (code "48") (name "TCK") (class "Default")
      (node (ref "J2") (pin "4") (pinfunction "TCK_4") (pintype "bidirectional"))
      (node (ref "U1") (pin "47") (pinfunction "JTAG_TCK_47") (pintype "bidirectional"))
    )
    (net (code "49") (name "TDI") (class "Default")
      (node (ref "U1") (pin "49") (pinfunction "PB6/JTAG-TDI_49") (pintype "bidirectional"))
    )
    (net (code "50") (name "TDO") (class "Default")
      (node (ref "J2") (pin "6") (pinfunction "TDO_6") (pintype "bidirectional"))
      (node (ref "U1") (pin "48") (pinfunction "PB7/JTAG-TDO_48") (pintype "bidirectional"))
    )
    (net (code "51") (name "TMS") (class "Default")
      (node (ref "J2") (pin "2") (pinfunction "TMS_2") (pintype "bidirectional"))
      (node (ref "U1") (pin "46") (pinfunction "JTAG_TMS_46") (pintype "bidirectional"))
    )
    (net (code "52") (name "USER_RELAY_CTRL") (class "Default")
      (node (ref "R15") (pin "2") (pinfunction "2_2") (pintype "passive"))
      (node (ref "S1") (pin "P$2") (pinfunction "P$2_P$2") (pintype "passive"))
      (node (ref "S1") (pin "P$4") (pinfunction "P$4_P$4") (pintype "passive"))
      (node (ref "U1") (pin "52") (pinfunction "PB3_52") (pintype "bidirectional"))
    )
    (net (code "53") (name "V1N") (class "Default")
      (node (ref "C9") (pin "1") (pinfunction "1_1") (pintype "passive"))
      (node (ref "R8") (pin "2") (pinfunction "2_2") (pintype "passive"))
      (node (ref "TP6") (pin "TESTPOINT") (pinfunction "TESTPOINT_TESTPOINT") (pintype "bidirectional"))
      (node (ref "U4") (pin "5") (pinfunction "V1N_5") (pintype "bidirectional"))
      (node (ref "U4") (pin "6") (pinfunction "V2N_6") (pintype "bidirectional"))
    )
    (net (code "54") (name "V1P") (class "Default")
      (node (ref "C8") (pin "1") (pinfunction "1_1") (pintype "passive"))
      (node (ref "R7") (pin "2") (pinfunction "2_2") (pintype "passive"))
      (node (ref "TP5") (pin "TESTPOINT") (pinfunction "TESTPOINT_TESTPOINT") (pintype "bidirectional"))
      (node (ref "U4") (pin "4") (pinfunction "V1P_4") (pintype "bidirectional"))
    )
    (net (code "55") (name "V2P") (class "Default")
      (node (ref "C10") (pin "1") (pinfunction "1_1") (pintype "passive"))
      (node (ref "R23") (pin "2") (pinfunction "2_2") (pintype "passive"))
      (node (ref "R9") (pin "2") (pinfunction "2_2") (pintype "passive"))
      (node (ref "TP7") (pin "TESTPOINT") (pinfunction "TESTPOINT_TESTPOINT") (pintype "bidirectional"))
      (node (ref "U4") (pin "7") (pinfunction "V2P_7") (pintype "bidirectional"))
    )
    (net (code "56") (name "VDC") (class "Default")
      (node (ref "C23") (pin "1") (pinfunction "1_1") (pintype "passive"))
      (node (ref "C28") (pin "1") (pinfunction "1_1") (pintype "passive"))
      (node (ref "C29") (pin "1") (pinfunction "1_1") (pintype "passive"))
      (node (ref "C34") (pin "+") (pinfunction "+_+") (pintype "bidirectional"))
      (node (ref "Q1") (pin "P$3") (pinfunction "E_P$3") (pintype "bidirectional"))
      (node (ref "R20") (pin "2") (pinfunction "2_2") (pintype "passive"))
      (node (ref "U6") (pin "6") (pinfunction "VOUT_6") (pintype "bidirectional"))
      (node (ref "U7") (pin "8") (pinfunction "VIN_8") (pintype "bidirectional"))
    )
    (net (code "57") (name "WALL_NEUTRAL") (class "Default")
      (node (ref "D1") (pin "CATHODE") (pinfunction "P$2_CATHODE") (pintype "bidirectional"))
      (node (ref "D2") (pin "2") (pinfunction "AC2_2") (pintype "bidirectional"))
      (node (ref "J5") (pin "NEUTRAL1") (pinfunction "NEUTRAL_NEUTRAL1") (pintype "bidirectional"))
      (node (ref "J5") (pin "NEUTRAL2") (pinfunction "NEUTRAL_NEUTRAL2") (pintype "bidirectional"))
      (node (ref "L2") (pin "P$1") (pinfunction "P$1_P$1") (pintype "bidirectional"))
      (node (ref "R1") (pin "1") (pinfunction "1_1") (pintype "passive"))
    )
    (net (code "58") (name "WALL_PHASE") (class "Default")
      (node (ref "D1") (pin "ANODE") (pinfunction "P$1_ANODE") (pintype "bidirectional"))
      (node (ref "D2") (pin "1") (pinfunction "AC1_1") (pintype "bidirectional"))
      (node (ref "J5") (pin "PHASE1") (pinfunction "PHASE_PHASE1") (pintype "bidirectional"))
      (node (ref "J5") (pin "PHASE2") (pinfunction "PHASE_PHASE2") (pintype "bidirectional"))
      (node (ref "K1") (pin "2") (pinfunction "2_2") (pintype "bidirectional"))
      (node (ref "L1") (pin "1") (pinfunction "P$1_1") (pintype "bidirectional"))
    )
    (net (code "59") (name "unconnected-(U1-DGND_USB-Pad1)") (class "Default")
      (node (ref "U1") (pin "1") (pinfunction "DGND_USB_1") (pintype "bidirectional"))
    )
    (net (code "60") (name "unconnected-(U1-DVDD_USB-Pad4)") (class "Default")
      (node (ref "U1") (pin "4") (pinfunction "DVDD_USB_4") (pintype "bidirectional"))
    )
    (net (code "61") (name "unconnected-(U1-PA0{slash}ROM-UART-RX-Pad16)") (class "Default")
      (node (ref "U1") (pin "16") (pinfunction "PA0/ROM-UART-RX_16") (pintype "bidirectional"))
    )
    (net (code "62") (name "unconnected-(U1-PA1{slash}ROM-UART-TX-Pad17)") (class "Default")
      (node (ref "U1") (pin "17") (pinfunction "PA1/ROM-UART-TX_17") (pintype "bidirectional"))
    )
    (net (code "63") (name "unconnected-(U1-PA2{slash}ROM-SSI-CLK-Pad18)") (class "Default")
      (node (ref "U1") (pin "18") (pinfunction "PA2/ROM-SSI-CLK_18") (pintype "bidirectional"))
    )
    (net (code "64") (name "unconnected-(U1-PA3{slash}ROM-SSI-SEL-Pad19)") (class "Default")
      (node (ref "U1") (pin "19") (pinfunction "PA3/ROM-SSI-SEL_19") (pintype "bidirectional"))
    )
    (net (code "65") (name "unconnected-(U1-PA4{slash}ROM-SSI-RX-Pad20)") (class "Default")
      (node (ref "U1") (pin "20") (pinfunction "PA4/ROM-SSI-RX_20") (pintype "bidirectional"))
    )
    (net (code "66") (name "unconnected-(U1-PA5{slash}ROM-SSI-TX-Pad21)") (class "Default")
      (node (ref "U1") (pin "21") (pinfunction "PA5/ROM-SSI-TX_21") (pintype "bidirectional"))
    )
    (net (code "67") (name "unconnected-(U1-PD0-Pad25)") (class "Default")
      (node (ref "U1") (pin "25") (pinfunction "PD0_25") (pintype "bidirectional"))
    )
    (net (code "68") (name "unconnected-(U1-PD1-Pad26)") (class "Default")
      (node (ref "U1") (pin "26") (pinfunction "PD1_26") (pintype "bidirectional"))
    )
    (net (code "69") (name "unconnected-(U1-PD2-Pad27)") (class "Default")
      (node (ref "U1") (pin "27") (pinfunction "PD2_27") (pintype "bidirectional"))
    )
    (net (code "70") (name "unconnected-(U1-PD3-Pad29)") (class "Default")
      (node (ref "U1") (pin "29") (pinfunction "PD3_29") (pintype "bidirectional"))
    )
    (net (code "71") (name "unconnected-(U1-PD4-Pad30)") (class "Default")
      (node (ref "U1") (pin "30") (pinfunction "PD4_30") (pintype "bidirectional"))
    )
    (net (code "72") (name "unconnected-(U1-PD5-Pad31)") (class "Default")
      (node (ref "U1") (pin "31") (pinfunction "PD5_31") (pintype "bidirectional"))
    )
    (net (code "73") (name "unconnected-(U1-USB_N-Pad3)") (class "Default")
      (node (ref "U1") (pin "3") (pinfunction "USB_N_3") (pintype "bidirectional"))
    )
    (net (code "74") (name "unconnected-(U1-USB_P-Pad2)") (class "Default")
      (node (ref "U1") (pin "2") (pinfunction "USB_P_2") (pintype "bidirectional"))
    )
    (net (code "75") (name "unconnected-(U4-~{SAG}-Pad13)") (class "Default")
      (node (ref "U4") (pin "13") (pinfunction "~{SAG}_13") (pintype "bidirectional"))
    )
    (net (code "76") (name "~{ADE_CS_5V}") (class "Default")
      (node (ref "U4") (pin "17") (pinfunction "~{CS}_17") (pintype "bidirectional"))
      (node (ref "U5") (pin "13") (pinfunction "B1_13") (pintype "bidirectional"))
    )
    (net (code "77") (name "~{ADE_CS}") (class "Default")
      (node (ref "TP4") (pin "TESTPOINT") (pinfunction "TESTPOINT_TESTPOINT") (pintype "bidirectional"))
      (node (ref "U1") (pin "53") (pinfunction "PB2_53") (pintype "bidirectional"))
      (node (ref "U5") (pin "2") (pinfunction "A1_2") (pintype "bidirectional"))
    )
    (net (code "78") (name "~{ADE_IRQ}") (class "Default")
      (node (ref "U1") (pin "54") (pinfunction "PB1_54") (pintype "bidirectional"))
      (node (ref "U4") (pin "14") (pinfunction "~{IRQ}_14") (pintype "bidirectional"))
    )
    (net (code "79") (name "~{ADE_RESET}") (class "Default")
      (node (ref "R16") (pin "2") (pinfunction "2_2") (pintype "passive"))
      (node (ref "U4") (pin "1") (pinfunction "~{RESET}_1") (pintype "bidirectional"))
    )
    (net (code "80") (name "~{FRAM_CS}") (class "Default")
      (node (ref "R12") (pin "1") (pinfunction "1_1") (pintype "passive"))
      (node (ref "U1") (pin "8") (pinfunction "PC5_8") (pintype "bidirectional"))
      (node (ref "U3") (pin "1") (pinfunction "~{CS}_1") (pintype "bidirectional"))
    )
    (net (code "81") (name "~{FRAM_HOLD}") (class "Default")
      (node (ref "R13") (pin "1") (pinfunction "1_1") (pintype "passive"))
      (node (ref "U1") (pin "13") (pinfunction "PC1_13") (pintype "bidirectional"))
      (node (ref "U3") (pin "7") (pinfunction "~{HOLD}_7") (pintype "bidirectional"))
    )
    (net (code "82") (name "~{FRAM_WP}") (class "Default")
      (node (ref "R14") (pin "1") (pinfunction "1_1") (pintype "passive"))
      (node (ref "U1") (pin "7") (pinfunction "PC6_7") (pintype "bidirectional"))
      (node (ref "U3") (pin "3") (pinfunction "~{WP}_3") (pintype "bidirectional"))
    )
    (net (code "83") (name "~{RESET}") (class "Default")
      (node (ref "J2") (pin "3") (pinfunction "~{RESET}_3") (pintype "bidirectional"))
      (node (ref "R11") (pin "1") (pinfunction "1_1") (pintype "passive"))
    )
  )
)
